# cubey.net
KiCad netlist of a schematic drawn in EAGLE
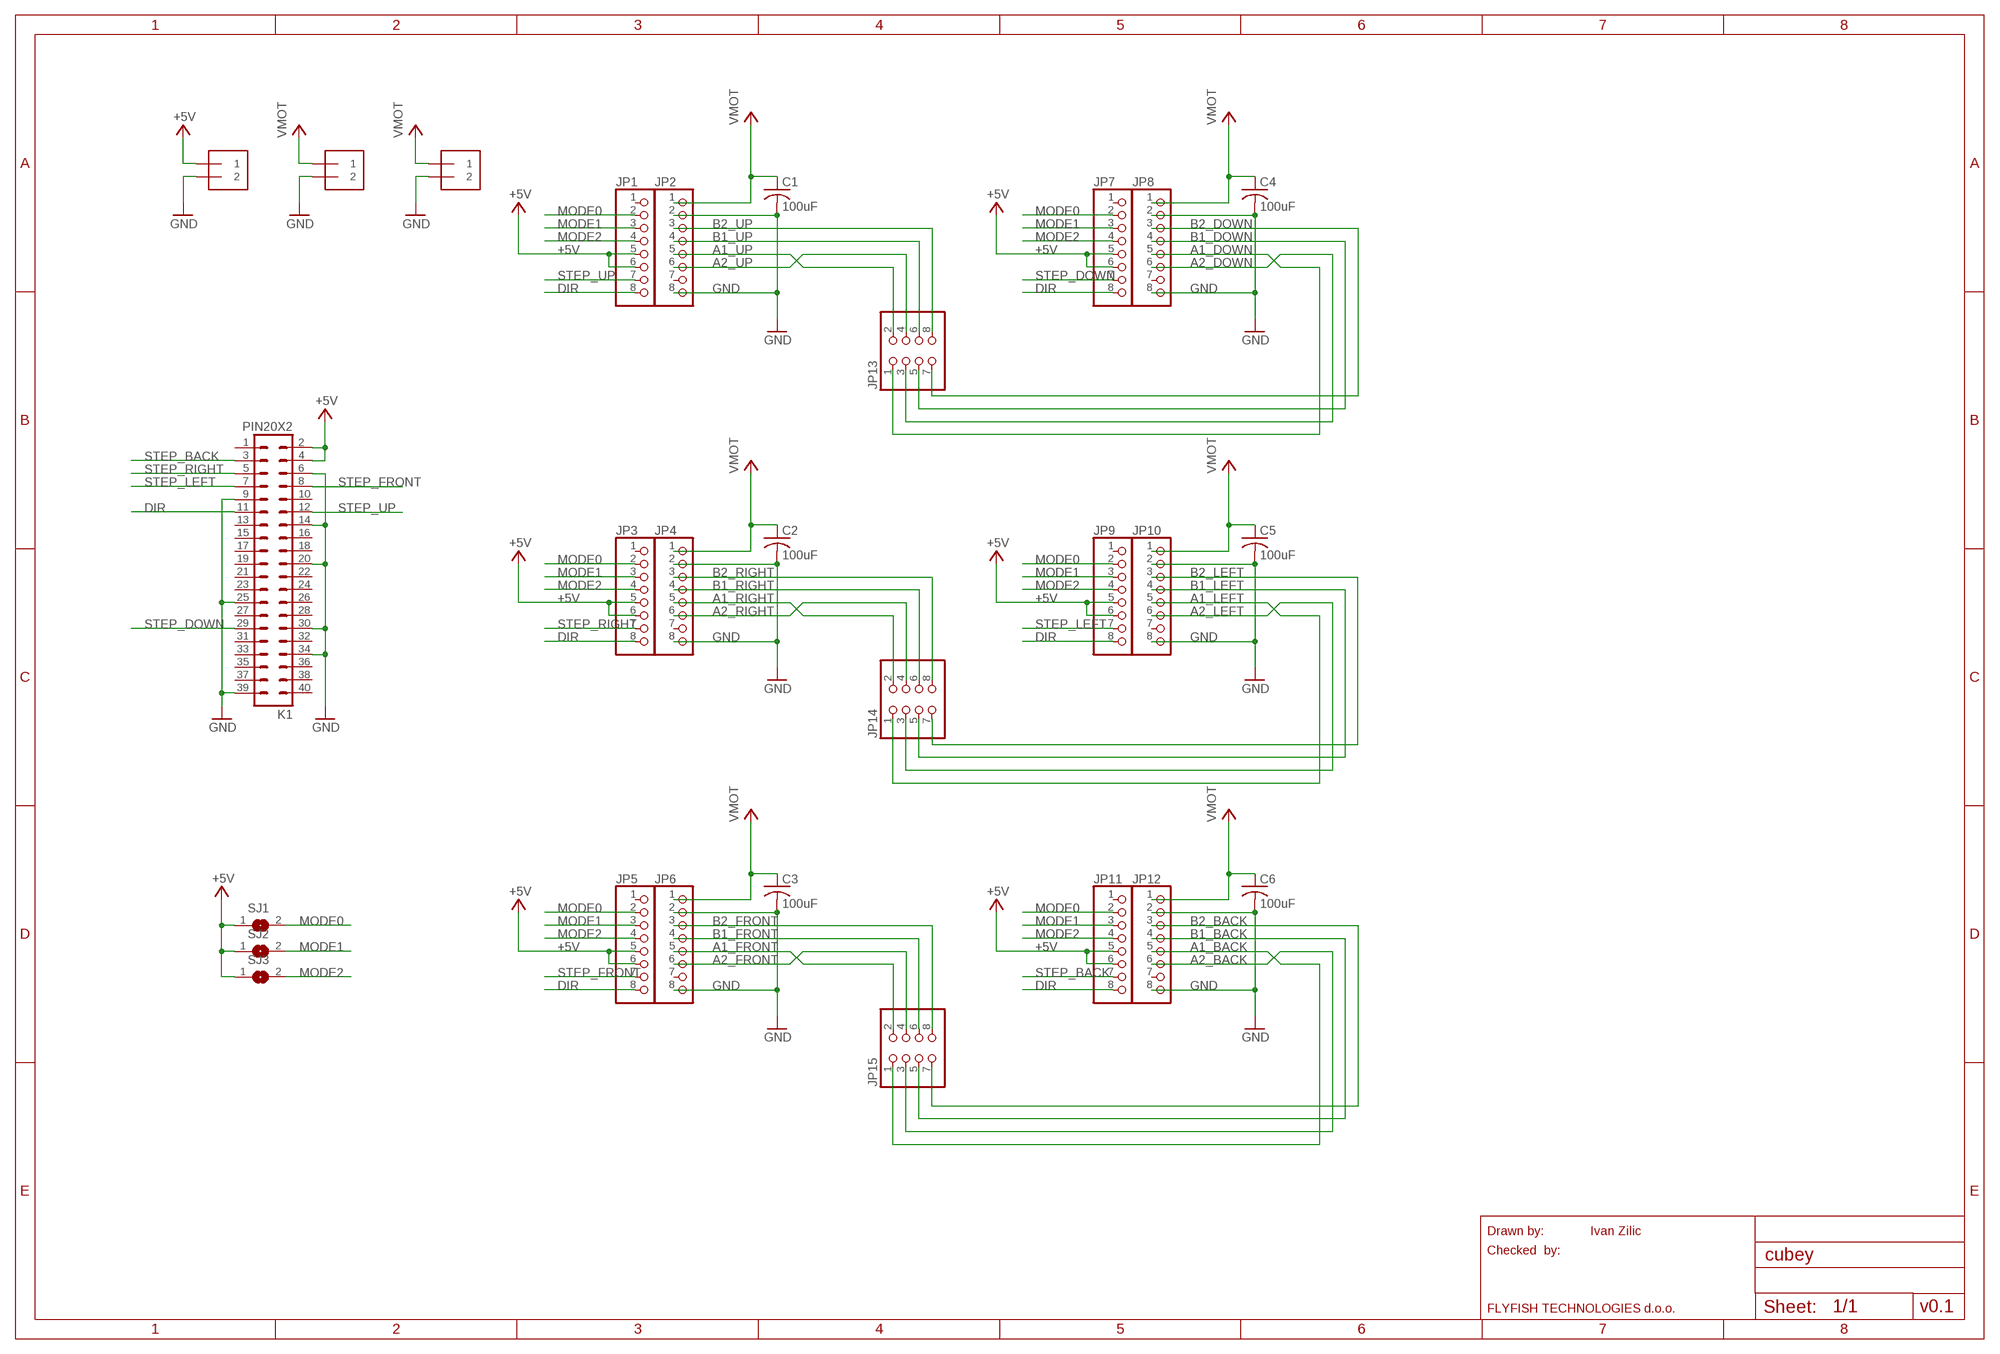
[diagram p0: schematic, sheet 1]

(export (version "E")
  (design (tool "Eeschema 10.0.6"))
  (components
    (comp (ref "5V_PWR")
      (value "1X2-3.5MM")
      (footprint "eagle-import:1X2-3.5MM")
      (libsource (lib "eagle-import") (part "1X2-3.5MM"))
    )
    (comp (ref "C1")
      (value "100uF")
      (footprint "eagle-import:C025-025X050")
      (libsource (lib "eagle-import") (part "C-US025-025X050"))
    )
    (comp (ref "C2")
      (value "100uF")
      (footprint "eagle-import:C025-025X050")
      (libsource (lib "eagle-import") (part "C-US025-025X050"))
    )
    (comp (ref "C3")
      (value "100uF")
      (footprint "eagle-import:C025-025X050")
      (libsource (lib "eagle-import") (part "C-US025-025X050"))
    )
    (comp (ref "C4")
      (value "100uF")
      (footprint "eagle-import:C025-025X050")
      (libsource (lib "eagle-import") (part "C-US025-025X050"))
    )
    (comp (ref "C5")
      (value "100uF")
      (footprint "eagle-import:C025-025X050")
      (libsource (lib "eagle-import") (part "C-US025-025X050"))
    )
    (comp (ref "C6")
      (value "100uF")
      (footprint "eagle-import:C025-025X050")
      (libsource (lib "eagle-import") (part "C-US025-025X050"))
    )
    (comp (ref "JP1")
      (value "PINHD-1X8")
      (footprint "eagle-import:1X08")
      (libsource (lib "eagle-import") (part "PINHD-1X8"))
    )
    (comp (ref "JP2")
      (value "PINHD-1X8")
      (footprint "eagle-import:1X08")
      (libsource (lib "eagle-import") (part "PINHD-1X8"))
    )
    (comp (ref "JP3")
      (value "PINHD-1X8")
      (footprint "eagle-import:1X08")
      (libsource (lib "eagle-import") (part "PINHD-1X8"))
    )
    (comp (ref "JP4")
      (value "PINHD-1X8")
      (footprint "eagle-import:1X08")
      (libsource (lib "eagle-import") (part "PINHD-1X8"))
    )
    (comp (ref "JP5")
      (value "PINHD-1X8")
      (footprint "eagle-import:1X08")
      (libsource (lib "eagle-import") (part "PINHD-1X8"))
    )
    (comp (ref "JP6")
      (value "PINHD-1X8")
      (footprint "eagle-import:1X08")
      (libsource (lib "eagle-import") (part "PINHD-1X8"))
    )
    (comp (ref "JP7")
      (value "PINHD-1X8")
      (footprint "eagle-import:1X08")
      (libsource (lib "eagle-import") (part "PINHD-1X8"))
    )
    (comp (ref "JP8")
      (value "PINHD-1X8")
      (footprint "eagle-import:1X08")
      (libsource (lib "eagle-import") (part "PINHD-1X8"))
    )
    (comp (ref "JP9")
      (value "PINHD-1X8")
      (footprint "eagle-import:1X08")
      (libsource (lib "eagle-import") (part "PINHD-1X8"))
    )
    (comp (ref "JP10")
      (value "PINHD-1X8")
      (footprint "eagle-import:1X08")
      (libsource (lib "eagle-import") (part "PINHD-1X8"))
    )
    (comp (ref "JP11")
      (value "PINHD-1X8")
      (footprint "eagle-import:1X08")
      (libsource (lib "eagle-import") (part "PINHD-1X8"))
    )
    (comp (ref "JP12")
      (value "PINHD-1X8")
      (footprint "eagle-import:1X08")
      (libsource (lib "eagle-import") (part "PINHD-1X8"))
    )
    (comp (ref "JP13")
      (value "PINHD-2X4")
      (footprint "eagle-import:2X04")
      (libsource (lib "eagle-import") (part "PINHD-2X4"))
    )
    (comp (ref "JP14")
      (value "PINHD-2X4")
      (footprint "eagle-import:2X04")
      (libsource (lib "eagle-import") (part "PINHD-2X4"))
    )
    (comp (ref "JP15")
      (value "PINHD-2X4")
      (footprint "eagle-import:2X04")
      (libsource (lib "eagle-import") (part "PINHD-2X4"))
    )
    (comp (ref "K1")
      (value "PIN20X2")
      (footprint "eagle-import:PIN_20X2")
      (libsource (lib "eagle-import") (part "PIN20X2"))
    )
    (comp (ref "MOT_PWR")
      (value "1X2-3.5MM")
      (footprint "eagle-import:1X2-3.5MM")
      (libsource (lib "eagle-import") (part "1X2-3.5MM"))
    )
    (comp (ref "MOT_PWR1")
      (value "1X2-3.5MM")
      (footprint "eagle-import:1X2-3.5MM")
      (libsource (lib "eagle-import") (part "1X2-3.5MM"))
    )
    (comp (ref "SJ1") (value "SJ") (footprint "eagle-import:SJ") (libsource (lib "eagle-import") (part "SJ")))
    (comp (ref "SJ2") (value "SJ") (footprint "eagle-import:SJ") (libsource (lib "eagle-import") (part "SJ")))
    (comp (ref "SJ3") (value "SJ") (footprint "eagle-import:SJ") (libsource (lib "eagle-import") (part "SJ")))
  )
  (nets
    (net (code "1") (name "+5V") (class "Default")
      (node (ref "5V_PWR") (pin "1") (pinfunction "1_1") (pintype "passive"))
      (node (ref "JP1") (pin "5") (pinfunction "5_5") (pintype "passive"))
      (node (ref "JP1") (pin "6") (pinfunction "6_6") (pintype "passive"))
      (node (ref "JP11") (pin "5") (pinfunction "5_5") (pintype "passive"))
      (node (ref "JP11") (pin "6") (pinfunction "6_6") (pintype "passive"))
      (node (ref "JP3") (pin "5") (pinfunction "5_5") (pintype "passive"))
      (node (ref "JP3") (pin "6") (pinfunction "6_6") (pintype "passive"))
      (node (ref "JP5") (pin "5") (pinfunction "5_5") (pintype "passive"))
      (node (ref "JP5") (pin "6") (pinfunction "6_6") (pintype "passive"))
      (node (ref "JP7") (pin "5") (pinfunction "5_5") (pintype "passive"))
      (node (ref "JP7") (pin "6") (pinfunction "6_6") (pintype "passive"))
      (node (ref "JP9") (pin "5") (pinfunction "5_5") (pintype "passive"))
      (node (ref "JP9") (pin "6") (pinfunction "6_6") (pintype "passive"))
      (node (ref "K1") (pin "2") (pinfunction "2_2") (pintype "passive"))
      (node (ref "K1") (pin "4") (pinfunction "4_4") (pintype "passive"))
      (node (ref "SJ1") (pin "1") (pinfunction "1_1") (pintype "passive"))
      (node (ref "SJ2") (pin "1") (pinfunction "1_1") (pintype "passive"))
      (node (ref "SJ3") (pin "1") (pinfunction "1_1") (pintype "passive"))
    )
    (net (code "2") (name "/A1_BACK") (class "Default")
      (node (ref "JP12") (pin "5") (pinfunction "5_5") (pintype "passive"))
      (node (ref "JP15") (pin "1") (pinfunction "1_1") (pintype "passive"))
    )
    (net (code "3") (name "/A1_DOWN") (class "Default")
      (node (ref "JP13") (pin "1") (pinfunction "1_1") (pintype "passive"))
      (node (ref "JP8") (pin "5") (pinfunction "5_5") (pintype "passive"))
    )
    (net (code "4") (name "/A1_FRONT") (class "Default")
      (node (ref "JP15") (pin "2") (pinfunction "2_2") (pintype "passive"))
      (node (ref "JP6") (pin "5") (pinfunction "5_5") (pintype "passive"))
    )
    (net (code "5") (name "/A1_LEFT") (class "Default")
      (node (ref "JP10") (pin "5") (pinfunction "5_5") (pintype "passive"))
      (node (ref "JP14") (pin "1") (pinfunction "1_1") (pintype "passive"))
    )
    (net (code "6") (name "/A1_RIGHT") (class "Default")
      (node (ref "JP14") (pin "2") (pinfunction "2_2") (pintype "passive"))
      (node (ref "JP4") (pin "5") (pinfunction "5_5") (pintype "passive"))
    )
    (net (code "7") (name "/A1_UP") (class "Default")
      (node (ref "JP13") (pin "2") (pinfunction "2_2") (pintype "passive"))
      (node (ref "JP2") (pin "5") (pinfunction "5_5") (pintype "passive"))
    )
    (net (code "8") (name "/A2_BACK") (class "Default")
      (node (ref "JP12") (pin "6") (pinfunction "6_6") (pintype "passive"))
      (node (ref "JP15") (pin "3") (pinfunction "3_3") (pintype "passive"))
    )
    (net (code "9") (name "/A2_DOWN") (class "Default")
      (node (ref "JP13") (pin "3") (pinfunction "3_3") (pintype "passive"))
      (node (ref "JP8") (pin "6") (pinfunction "6_6") (pintype "passive"))
    )
    (net (code "10") (name "/A2_FRONT") (class "Default")
      (node (ref "JP15") (pin "4") (pinfunction "4_4") (pintype "passive"))
      (node (ref "JP6") (pin "6") (pinfunction "6_6") (pintype "passive"))
    )
    (net (code "11") (name "/A2_LEFT") (class "Default")
      (node (ref "JP10") (pin "6") (pinfunction "6_6") (pintype "passive"))
      (node (ref "JP14") (pin "3") (pinfunction "3_3") (pintype "passive"))
    )
    (net (code "12") (name "/A2_RIGHT") (class "Default")
      (node (ref "JP14") (pin "4") (pinfunction "4_4") (pintype "passive"))
      (node (ref "JP4") (pin "6") (pinfunction "6_6") (pintype "passive"))
    )
    (net (code "13") (name "/A2_UP") (class "Default")
      (node (ref "JP13") (pin "4") (pinfunction "4_4") (pintype "passive"))
      (node (ref "JP2") (pin "6") (pinfunction "6_6") (pintype "passive"))
    )
    (net (code "14") (name "/B1_BACK") (class "Default")
      (node (ref "JP12") (pin "4") (pinfunction "4_4") (pintype "passive"))
      (node (ref "JP15") (pin "5") (pinfunction "5_5") (pintype "passive"))
    )
    (net (code "15") (name "/B1_DOWN") (class "Default")
      (node (ref "JP13") (pin "5") (pinfunction "5_5") (pintype "passive"))
      (node (ref "JP8") (pin "4") (pinfunction "4_4") (pintype "passive"))
    )
    (net (code "16") (name "/B1_FRONT") (class "Default")
      (node (ref "JP15") (pin "6") (pinfunction "6_6") (pintype "passive"))
      (node (ref "JP6") (pin "4") (pinfunction "4_4") (pintype "passive"))
    )
    (net (code "17") (name "/B1_LEFT") (class "Default")
      (node (ref "JP10") (pin "4") (pinfunction "4_4") (pintype "passive"))
      (node (ref "JP14") (pin "5") (pinfunction "5_5") (pintype "passive"))
    )
    (net (code "18") (name "/B1_RIGHT") (class "Default")
      (node (ref "JP14") (pin "6") (pinfunction "6_6") (pintype "passive"))
      (node (ref "JP4") (pin "4") (pinfunction "4_4") (pintype "passive"))
    )
    (net (code "19") (name "/B1_UP") (class "Default")
      (node (ref "JP13") (pin "6") (pinfunction "6_6") (pintype "passive"))
      (node (ref "JP2") (pin "4") (pinfunction "4_4") (pintype "passive"))
    )
    (net (code "20") (name "/B2_BACK") (class "Default")
      (node (ref "JP12") (pin "3") (pinfunction "3_3") (pintype "passive"))
      (node (ref "JP15") (pin "7") (pinfunction "7_7") (pintype "passive"))
    )
    (net (code "21") (name "/B2_DOWN") (class "Default")
      (node (ref "JP13") (pin "7") (pinfunction "7_7") (pintype "passive"))
      (node (ref "JP8") (pin "3") (pinfunction "3_3") (pintype "passive"))
    )
    (net (code "22") (name "/B2_FRONT") (class "Default")
      (node (ref "JP15") (pin "8") (pinfunction "8_8") (pintype "passive"))
      (node (ref "JP6") (pin "3") (pinfunction "3_3") (pintype "passive"))
    )
    (net (code "23") (name "/B2_LEFT") (class "Default")
      (node (ref "JP10") (pin "3") (pinfunction "3_3") (pintype "passive"))
      (node (ref "JP14") (pin "7") (pinfunction "7_7") (pintype "passive"))
    )
    (net (code "24") (name "/B2_RIGHT") (class "Default")
      (node (ref "JP14") (pin "8") (pinfunction "8_8") (pintype "passive"))
      (node (ref "JP4") (pin "3") (pinfunction "3_3") (pintype "passive"))
    )
    (net (code "25") (name "/B2_UP") (class "Default")
      (node (ref "JP13") (pin "8") (pinfunction "8_8") (pintype "passive"))
      (node (ref "JP2") (pin "3") (pinfunction "3_3") (pintype "passive"))
    )
    (net (code "26") (name "/DIR") (class "Default")
      (node (ref "JP1") (pin "8") (pinfunction "8_8") (pintype "passive"))
      (node (ref "JP11") (pin "8") (pinfunction "8_8") (pintype "passive"))
      (node (ref "JP3") (pin "8") (pinfunction "8_8") (pintype "passive"))
      (node (ref "JP5") (pin "8") (pinfunction "8_8") (pintype "passive"))
      (node (ref "JP7") (pin "8") (pinfunction "8_8") (pintype "passive"))
      (node (ref "JP9") (pin "8") (pinfunction "8_8") (pintype "passive"))
      (node (ref "K1") (pin "11") (pinfunction "11_11") (pintype "passive"))
    )
    (net (code "27") (name "/MODE0") (class "Default")
      (node (ref "JP1") (pin "2") (pinfunction "2_2") (pintype "passive"))
      (node (ref "JP11") (pin "2") (pinfunction "2_2") (pintype "passive"))
      (node (ref "JP3") (pin "2") (pinfunction "2_2") (pintype "passive"))
      (node (ref "JP5") (pin "2") (pinfunction "2_2") (pintype "passive"))
      (node (ref "JP7") (pin "2") (pinfunction "2_2") (pintype "passive"))
      (node (ref "JP9") (pin "2") (pinfunction "2_2") (pintype "passive"))
      (node (ref "SJ1") (pin "2") (pinfunction "2_2") (pintype "passive"))
    )
    (net (code "28") (name "/MODE1") (class "Default")
      (node (ref "JP1") (pin "3") (pinfunction "3_3") (pintype "passive"))
      (node (ref "JP11") (pin "3") (pinfunction "3_3") (pintype "passive"))
      (node (ref "JP3") (pin "3") (pinfunction "3_3") (pintype "passive"))
      (node (ref "JP5") (pin "3") (pinfunction "3_3") (pintype "passive"))
      (node (ref "JP7") (pin "3") (pinfunction "3_3") (pintype "passive"))
      (node (ref "JP9") (pin "3") (pinfunction "3_3") (pintype "passive"))
      (node (ref "SJ2") (pin "2") (pinfunction "2_2") (pintype "passive"))
    )
    (net (code "29") (name "/MODE2") (class "Default")
      (node (ref "JP1") (pin "4") (pinfunction "4_4") (pintype "passive"))
      (node (ref "JP11") (pin "4") (pinfunction "4_4") (pintype "passive"))
      (node (ref "JP3") (pin "4") (pinfunction "4_4") (pintype "passive"))
      (node (ref "JP5") (pin "4") (pinfunction "4_4") (pintype "passive"))
      (node (ref "JP7") (pin "4") (pinfunction "4_4") (pintype "passive"))
      (node (ref "JP9") (pin "4") (pinfunction "4_4") (pintype "passive"))
      (node (ref "SJ3") (pin "2") (pinfunction "2_2") (pintype "passive"))
    )
    (net (code "30") (name "/STEP_BACK") (class "Default")
      (node (ref "JP11") (pin "7") (pinfunction "7_7") (pintype "passive"))
      (node (ref "K1") (pin "3") (pinfunction "3_3") (pintype "passive"))
    )
    (net (code "31") (name "/STEP_DOWN") (class "Default")
      (node (ref "JP7") (pin "7") (pinfunction "7_7") (pintype "passive"))
      (node (ref "K1") (pin "29") (pinfunction "29_29") (pintype "passive"))
    )
    (net (code "32") (name "/STEP_FRONT") (class "Default")
      (node (ref "JP5") (pin "7") (pinfunction "7_7") (pintype "passive"))
      (node (ref "K1") (pin "8") (pinfunction "8_8") (pintype "passive"))
    )
    (net (code "33") (name "/STEP_LEFT") (class "Default")
      (node (ref "JP9") (pin "7") (pinfunction "7_7") (pintype "passive"))
      (node (ref "K1") (pin "7") (pinfunction "7_7") (pintype "passive"))
    )
    (net (code "34") (name "/STEP_RIGHT") (class "Default")
      (node (ref "JP3") (pin "7") (pinfunction "7_7") (pintype "passive"))
      (node (ref "K1") (pin "5") (pinfunction "5_5") (pintype "passive"))
    )
    (net (code "35") (name "/STEP_UP") (class "Default")
      (node (ref "JP1") (pin "7") (pinfunction "7_7") (pintype "passive"))
      (node (ref "K1") (pin "12") (pinfunction "12_12") (pintype "passive"))
    )
    (net (code "36") (name "GND") (class "Default")
      (node (ref "5V_PWR") (pin "2") (pinfunction "2_2") (pintype "passive"))
      (node (ref "C1") (pin "2") (pinfunction "2_2") (pintype "passive"))
      (node (ref "C2") (pin "2") (pinfunction "2_2") (pintype "passive"))
      (node (ref "C3") (pin "2") (pinfunction "2_2") (pintype "passive"))
      (node (ref "C4") (pin "2") (pinfunction "2_2") (pintype "passive"))
      (node (ref "C5") (pin "2") (pinfunction "2_2") (pintype "passive"))
      (node (ref "C6") (pin "2") (pinfunction "2_2") (pintype "passive"))
      (node (ref "JP10") (pin "2") (pinfunction "2_2") (pintype "passive"))
      (node (ref "JP10") (pin "8") (pinfunction "8_8") (pintype "passive"))
      (node (ref "JP12") (pin "2") (pinfunction "2_2") (pintype "passive"))
      (node (ref "JP12") (pin "8") (pinfunction "8_8") (pintype "passive"))
      (node (ref "JP2") (pin "2") (pinfunction "2_2") (pintype "passive"))
      (node (ref "JP2") (pin "8") (pinfunction "8_8") (pintype "passive"))
      (node (ref "JP4") (pin "2") (pinfunction "2_2") (pintype "passive"))
      (node (ref "JP4") (pin "8") (pinfunction "8_8") (pintype "passive"))
      (node (ref "JP6") (pin "2") (pinfunction "2_2") (pintype "passive"))
      (node (ref "JP6") (pin "8") (pinfunction "8_8") (pintype "passive"))
      (node (ref "JP8") (pin "2") (pinfunction "2_2") (pintype "passive"))
      (node (ref "JP8") (pin "8") (pinfunction "8_8") (pintype "passive"))
      (node (ref "K1") (pin "14") (pinfunction "14_14") (pintype "passive"))
      (node (ref "K1") (pin "20") (pinfunction "20_20") (pintype "passive"))
      (node (ref "K1") (pin "25") (pinfunction "25_25") (pintype "passive"))
      (node (ref "K1") (pin "30") (pinfunction "30_30") (pintype "passive"))
      (node (ref "K1") (pin "34") (pinfunction "34_34") (pintype "passive"))
      (node (ref "K1") (pin "39") (pinfunction "39_39") (pintype "passive"))
      (node (ref "K1") (pin "6") (pinfunction "6_6") (pintype "passive"))
      (node (ref "K1") (pin "9") (pinfunction "9_9") (pintype "passive"))
      (node (ref "MOT_PWR") (pin "2") (pinfunction "2_2") (pintype "passive"))
      (node (ref "MOT_PWR1") (pin "2") (pinfunction "2_2") (pintype "passive"))
    )
    (net (code "37") (name "VMOT") (class "Default")
      (node (ref "C1") (pin "1") (pinfunction "1_1") (pintype "passive"))
      (node (ref "C2") (pin "1") (pinfunction "1_1") (pintype "passive"))
      (node (ref "C3") (pin "1") (pinfunction "1_1") (pintype "passive"))
      (node (ref "C4") (pin "1") (pinfunction "1_1") (pintype "passive"))
      (node (ref "C5") (pin "1") (pinfunction "1_1") (pintype "passive"))
      (node (ref "C6") (pin "1") (pinfunction "1_1") (pintype "passive"))
      (node (ref "JP10") (pin "1") (pinfunction "1_1") (pintype "passive"))
      (node (ref "JP12") (pin "1") (pinfunction "1_1") (pintype "passive"))
      (node (ref "JP2") (pin "1") (pinfunction "1_1") (pintype "passive"))
      (node (ref "JP4") (pin "1") (pinfunction "1_1") (pintype "passive"))
      (node (ref "JP6") (pin "1") (pinfunction "1_1") (pintype "passive"))
      (node (ref "JP8") (pin "1") (pinfunction "1_1") (pintype "passive"))
      (node (ref "MOT_PWR") (pin "1") (pinfunction "1_1") (pintype "passive"))
      (node (ref "MOT_PWR1") (pin "1") (pinfunction "1_1") (pintype "passive"))
    )
    (net (code "38") (name "unconnected-(JP1-Pad1)") (class "Default")
      (node (ref "JP1") (pin "1") (pinfunction "1_1") (pintype "passive"))
    )
    (net (code "39") (name "unconnected-(JP2-Pad7)") (class "Default")
      (node (ref "JP2") (pin "7") (pinfunction "7_7") (pintype "passive"))
    )
    (net (code "40") (name "unconnected-(JP3-Pad1)") (class "Default")
      (node (ref "JP3") (pin "1") (pinfunction "1_1") (pintype "passive"))
    )
    (net (code "41") (name "unconnected-(JP4-Pad7)") (class "Default")
      (node (ref "JP4") (pin "7") (pinfunction "7_7") (pintype "passive"))
    )
    (net (code "42") (name "unconnected-(JP5-Pad1)") (class "Default")
      (node (ref "JP5") (pin "1") (pinfunction "1_1") (pintype "passive"))
    )
    (net (code "43") (name "unconnected-(JP6-Pad7)") (class "Default")
      (node (ref "JP6") (pin "7") (pinfunction "7_7") (pintype "passive"))
    )
    (net (code "44") (name "unconnected-(JP7-Pad1)") (class "Default")
      (node (ref "JP7") (pin "1") (pinfunction "1_1") (pintype "passive"))
    )
    (net (code "45") (name "unconnected-(JP8-Pad7)") (class "Default")
      (node (ref "JP8") (pin "7") (pinfunction "7_7") (pintype "passive"))
    )
    (net (code "46") (name "unconnected-(JP9-Pad1)") (class "Default")
      (node (ref "JP9") (pin "1") (pinfunction "1_1") (pintype "passive"))
    )
    (net (code "47") (name "unconnected-(JP10-Pad7)") (class "Default")
      (node (ref "JP10") (pin "7") (pinfunction "7_7") (pintype "passive"))
    )
    (net (code "48") (name "unconnected-(JP11-Pad1)") (class "Default")
      (node (ref "JP11") (pin "1") (pinfunction "1_1") (pintype "passive"))
    )
    (net (code "49") (name "unconnected-(JP12-Pad7)") (class "Default")
      (node (ref "JP12") (pin "7") (pinfunction "7_7") (pintype "passive"))
    )
    (net (code "50") (name "unconnected-(K1-Pad1)") (class "Default")
      (node (ref "K1") (pin "1") (pinfunction "1_1") (pintype "passive"))
    )
    (net (code "51") (name "unconnected-(K1-Pad10)") (class "Default")
      (node (ref "K1") (pin "10") (pinfunction "10_10") (pintype "passive"))
    )
    (net (code "52") (name "unconnected-(K1-Pad13)") (class "Default")
      (node (ref "K1") (pin "13") (pinfunction "13_13") (pintype "passive"))
    )
    (net (code "53") (name "unconnected-(K1-Pad15)") (class "Default")
      (node (ref "K1") (pin "15") (pinfunction "15_15") (pintype "passive"))
    )
    (net (code "54") (name "unconnected-(K1-Pad16)") (class "Default")
      (node (ref "K1") (pin "16") (pinfunction "16_16") (pintype "passive"))
    )
    (net (code "55") (name "unconnected-(K1-Pad17)") (class "Default")
      (node (ref "K1") (pin "17") (pinfunction "17_17") (pintype "passive"))
    )
    (net (code "56") (name "unconnected-(K1-Pad18)") (class "Default")
      (node (ref "K1") (pin "18") (pinfunction "18_18") (pintype "passive"))
    )
    (net (code "57") (name "unconnected-(K1-Pad19)") (class "Default")
      (node (ref "K1") (pin "19") (pinfunction "19_19") (pintype "passive"))
    )
    (net (code "58") (name "unconnected-(K1-Pad21)") (class "Default")
      (node (ref "K1") (pin "21") (pinfunction "21_21") (pintype "passive"))
    )
    (net (code "59") (name "unconnected-(K1-Pad22)") (class "Default")
      (node (ref "K1") (pin "22") (pinfunction "22_22") (pintype "passive"))
    )
    (net (code "60") (name "unconnected-(K1-Pad23)") (class "Default")
      (node (ref "K1") (pin "23") (pinfunction "23_23") (pintype "passive"))
    )
    (net (code "61") (name "unconnected-(K1-Pad24)") (class "Default")
      (node (ref "K1") (pin "24") (pinfunction "24_24") (pintype "passive"))
    )
    (net (code "62") (name "unconnected-(K1-Pad26)") (class "Default")
      (node (ref "K1") (pin "26") (pinfunction "26_26") (pintype "passive"))
    )
    (net (code "63") (name "unconnected-(K1-Pad27)") (class "Default")
      (node (ref "K1") (pin "27") (pinfunction "27_27") (pintype "passive"))
    )
    (net (code "64") (name "unconnected-(K1-Pad28)") (class "Default")
      (node (ref "K1") (pin "28") (pinfunction "28_28") (pintype "passive"))
    )
    (net (code "65") (name "unconnected-(K1-Pad31)") (class "Default")
      (node (ref "K1") (pin "31") (pinfunction "31_31") (pintype "passive"))
    )
    (net (code "66") (name "unconnected-(K1-Pad32)") (class "Default")
      (node (ref "K1") (pin "32") (pinfunction "32_32") (pintype "passive"))
    )
    (net (code "67") (name "unconnected-(K1-Pad33)") (class "Default")
      (node (ref "K1") (pin "33") (pinfunction "33_33") (pintype "passive"))
    )
    (net (code "68") (name "unconnected-(K1-Pad35)") (class "Default")
      (node (ref "K1") (pin "35") (pinfunction "35_35") (pintype "passive"))
    )
    (net (code "69") (name "unconnected-(K1-Pad36)") (class "Default")
      (node (ref "K1") (pin "36") (pinfunction "36_36") (pintype "passive"))
    )
    (net (code "70") (name "unconnected-(K1-Pad37)") (class "Default")
      (node (ref "K1") (pin "37") (pinfunction "37_37") (pintype "passive"))
    )
    (net (code "71") (name "unconnected-(K1-Pad38)") (class "Default")
      (node (ref "K1") (pin "38") (pinfunction "38_38") (pintype "passive"))
    )
    (net (code "72") (name "unconnected-(K1-Pad40)") (class "Default")
      (node (ref "K1") (pin "40") (pinfunction "40_40") (pintype "passive"))
    )
  )
)
